# Control.net
KiCad netlist of a schematic drawn in EAGLE
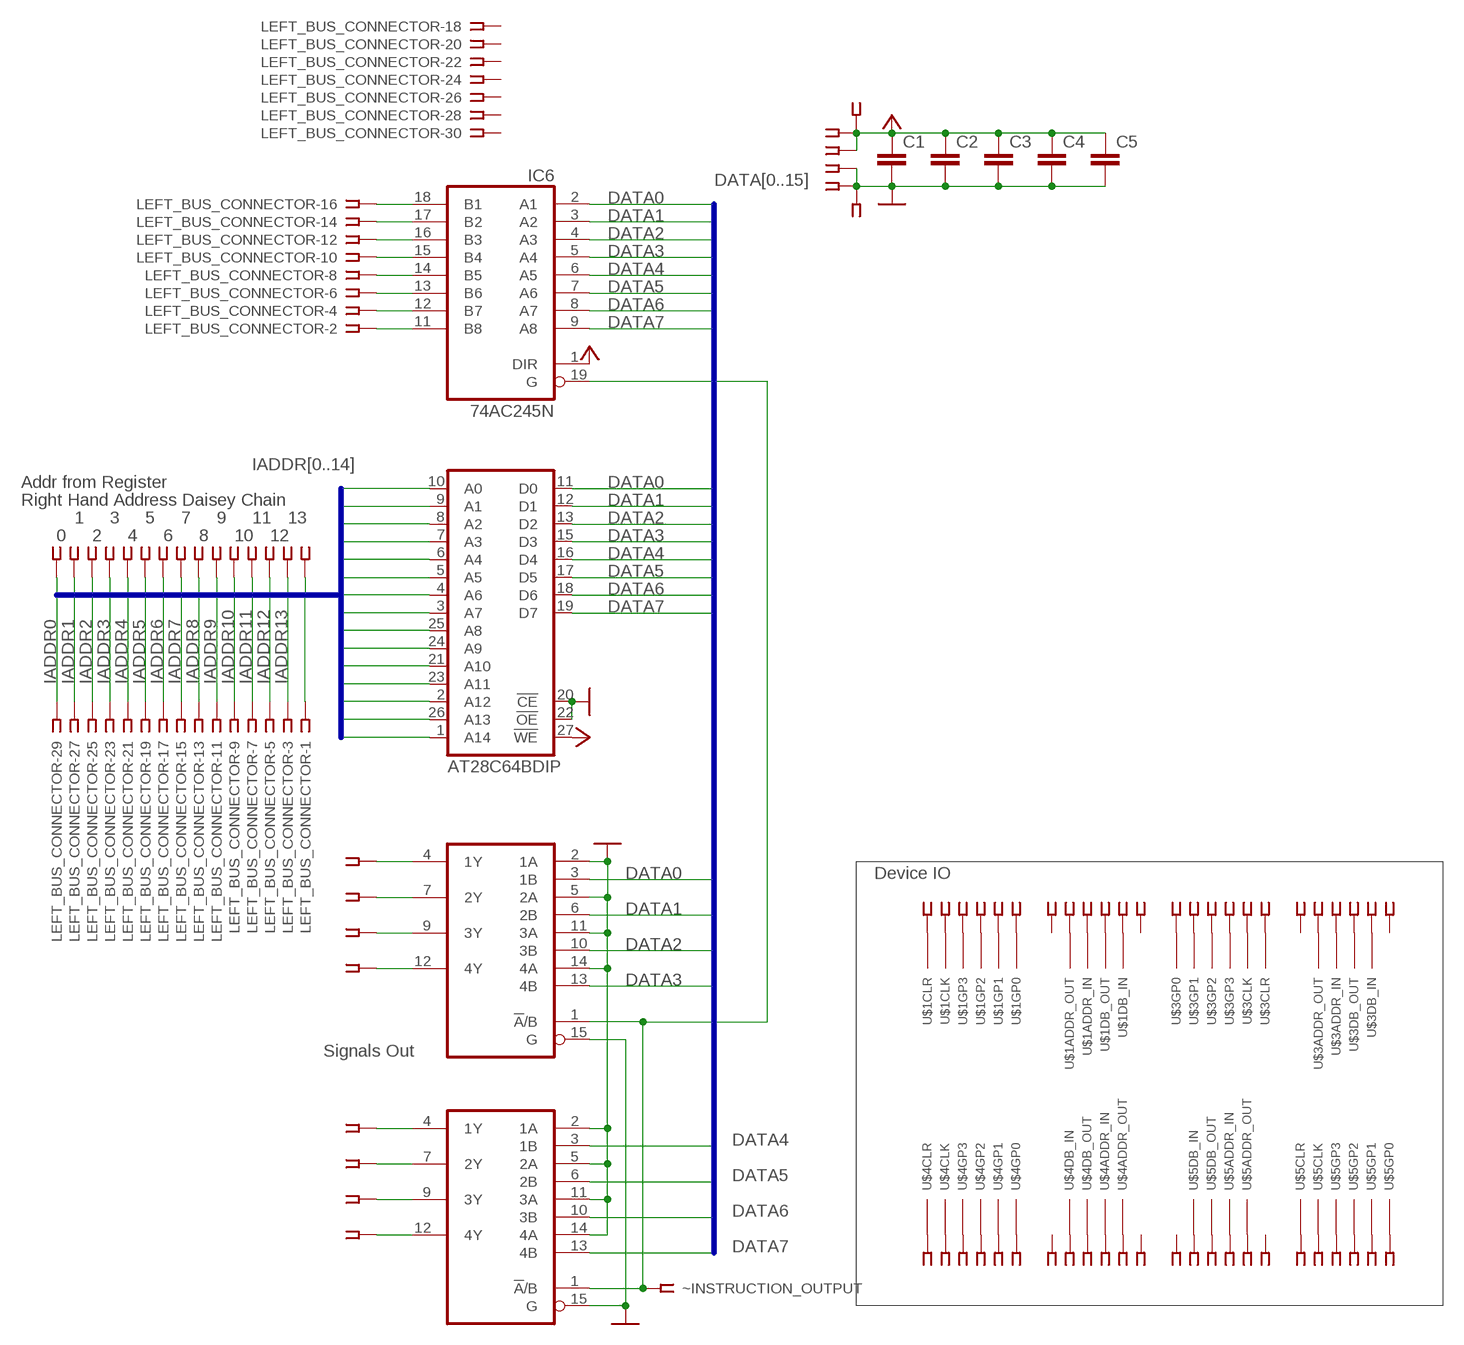
[diagram p0: schematic, sheet 1]

(export (version "E")
  (design (tool "Eeschema 10.0.6"))
  (components
    (comp (ref "C1")
      (value "C2.5/2")
      (footprint "eagle-import:C2.5-2")
      (libsource (lib "eagle-import") (part "C2.5/2"))
    )
    (comp (ref "C2")
      (value "C2.5/2")
      (footprint "eagle-import:C2.5-2")
      (libsource (lib "eagle-import") (part "C2.5/2"))
    )
    (comp (ref "C3")
      (value "C2.5/2")
      (footprint "eagle-import:C2.5-2")
      (libsource (lib "eagle-import") (part "C2.5/2"))
    )
    (comp (ref "C4")
      (value "C2.5/2")
      (footprint "eagle-import:C2.5-2")
      (libsource (lib "eagle-import") (part "C2.5/2"))
    )
    (comp (ref "C5")
      (value "C2.5/2")
      (footprint "eagle-import:C2.5-2")
      (libsource (lib "eagle-import") (part "C2.5/2"))
    )
    (comp (ref "IC4")
      (value "74AC157N")
      (footprint "eagle-import:DIL16")
      (libsource (lib "eagle-import") (part "74157NAC"))
    )
    (comp (ref "IC5")
      (value "74AC157N")
      (footprint "eagle-import:DIL16")
      (libsource (lib "eagle-import") (part "74157NAC"))
    )
    (comp (ref "IC6")
      (value "74AC245N")
      (footprint "eagle-import:DIL20")
      (libsource (lib "eagle-import") (part "74245NAC"))
    )
    (comp (ref "LEFT_BUS_CONNECTOR")
      (value "SSW-115-02-G-D")
      (footprint "eagle-import:SSW-115-02-G-D")
      (fields (field (name "MF") "Samtec Inc."))
      (libsource (lib "eagle-import") (part "SSW-115-02-G-D"))
    )
    (comp (ref "MEZZANINE")
      (value "SSW-104-02-G-S")
      (footprint "eagle-import:SSW-104-02-G-S")
      (fields (field (name "MF") "Samtec Inc."))
      (libsource (lib "eagle-import") (part "SSW-104-02-G-S"))
    )
    (comp (ref "U$1")
      (value "CONTROL_SIG-INT")
      (footprint "eagle-import:CONTROL_SIG-INT-FOOT")
      (libsource (lib "eagle-import") (part "CONTROL_SIG-INT"))
    )
    (comp (ref "U$2")
      (value "AT28C64BDIP")
      (footprint "eagle-import:DIP28-WIDE")
      (libsource (lib "eagle-import") (part "AT28C64BDIP"))
    )
    (comp (ref "U$3")
      (value "CONTROL_SIG-INT")
      (footprint "eagle-import:CONTROL_SIG-INT-FOOT")
      (libsource (lib "eagle-import") (part "CONTROL_SIG-INT"))
    )
    (comp (ref "U$4")
      (value "CONTROL_SIG-INT")
      (footprint "eagle-import:CONTROL_SIG-INT-FOOT")
      (libsource (lib "eagle-import") (part "CONTROL_SIG-INT"))
    )
    (comp (ref "U$5")
      (value "CONTROL_SIG-INT")
      (footprint "eagle-import:CONTROL_SIG-INT-FOOT")
      (libsource (lib "eagle-import") (part "CONTROL_SIG-INT"))
    )
    (comp (ref "X1")
      (value "SSW-106-02-G-S")
      (footprint "eagle-import:SSW-106-02-G-S")
      (fields (field (name "MF") "Samtec Inc."))
      (libsource (lib "eagle-import") (part "SSW-106-02-G-S"))
    )
    (comp (ref "X2")
      (value "SSW-106-02-G-S")
      (footprint "eagle-import:SSW-106-02-G-S")
      (fields (field (name "MF") "Samtec Inc."))
      (libsource (lib "eagle-import") (part "SSW-106-02-G-S"))
    )
    (comp (ref "X3")
      (value "SSW-106-02-G-S")
      (footprint "eagle-import:SSW-106-02-G-S")
      (fields (field (name "MF") "Samtec Inc."))
      (libsource (lib "eagle-import") (part "SSW-106-02-G-S"))
    )
    (comp (ref "X4")
      (value "SSW-106-02-G-S")
      (footprint "eagle-import:SSW-106-02-G-S")
      (fields (field (name "MF") "Samtec Inc."))
      (libsource (lib "eagle-import") (part "SSW-106-02-G-S"))
    )
    (comp (ref "X5")
      (value "SSW-108-02-G-S")
      (footprint "eagle-import:SSW-108-02-G-S")
      (fields (field (name "MF") "Samtec Inc."))
      (libsource (lib "eagle-import") (part "SSW-108-02-G-S"))
    )
    (comp (ref "X6")
      (value "SSW-106-02-G-S")
      (footprint "eagle-import:SSW-106-02-G-S")
      (fields (field (name "MF") "Samtec Inc."))
      (libsource (lib "eagle-import") (part "SSW-106-02-G-S"))
    )
    (comp (ref "X7")
      (value "SSW-106-02-G-S")
      (footprint "eagle-import:SSW-106-02-G-S")
      (fields (field (name "MF") "Samtec Inc."))
      (libsource (lib "eagle-import") (part "SSW-106-02-G-S"))
    )
    (comp (ref "X8")
      (value "SSW-106-02-G-S")
      (footprint "eagle-import:SSW-106-02-G-S")
      (fields (field (name "MF") "Samtec Inc."))
      (libsource (lib "eagle-import") (part "SSW-106-02-G-S"))
    )
    (comp (ref "X9")
      (value "SSW-106-02-G-S")
      (footprint "eagle-import:SSW-106-02-G-S")
      (fields (field (name "MF") "Samtec Inc."))
      (libsource (lib "eagle-import") (part "SSW-106-02-G-S"))
    )
    (comp (ref "X11")
      (value "SSW-102-02-G-S")
      (footprint "eagle-import:SSW-102-02-G-S")
      (fields (field (name "MF") "Samtec Inc."))
      (libsource (lib "eagle-import") (part "SSW-102-02-G-S"))
    )
    (comp (ref "X12")
      (value "SSW-115-02-G-S")
      (footprint "eagle-import:SSW-115-02-G-S")
      (fields (field (name "MF") "Samtec Inc."))
      (libsource (lib "eagle-import") (part "SSW-115-02-G-S"))
    )
    (comp (ref "~INSTRUCTION_OUTPUT")
      (value "SSW-101-02-G-S")
      (footprint "eagle-import:SSW-101-02-G-S")
      (fields (field (name "MF") "Samtec Inc."))
      (libsource (lib "eagle-import") (part "SSW-101-02-G-S"))
    )
  )
  (nets
    (net (code "1") (name "/DATA0") (class "Default")
      (node (ref "IC4") (pin "3") (pinfunction "1B_3") (pintype "input"))
      (node (ref "IC6") (pin "2") (pinfunction "A1_2") (pintype "bidirectional"))
      (node (ref "U$2") (pin "11") (pinfunction "D0_11") (pintype "bidirectional"))
    )
    (net (code "2") (name "/DATA1") (class "Default")
      (node (ref "IC4") (pin "6") (pinfunction "2B_6") (pintype "input"))
      (node (ref "IC6") (pin "3") (pinfunction "A2_3") (pintype "bidirectional"))
      (node (ref "U$2") (pin "12") (pinfunction "D1_12") (pintype "bidirectional"))
    )
    (net (code "3") (name "/DATA2") (class "Default")
      (node (ref "IC4") (pin "10") (pinfunction "3B_10") (pintype "input"))
      (node (ref "IC6") (pin "4") (pinfunction "A3_4") (pintype "bidirectional"))
      (node (ref "U$2") (pin "13") (pinfunction "D2_13") (pintype "bidirectional"))
    )
    (net (code "4") (name "/DATA3") (class "Default")
      (node (ref "IC4") (pin "13") (pinfunction "4B_13") (pintype "input"))
      (node (ref "IC6") (pin "5") (pinfunction "A4_5") (pintype "bidirectional"))
      (node (ref "U$2") (pin "15") (pinfunction "D3_15") (pintype "bidirectional"))
    )
    (net (code "5") (name "/DATA4") (class "Default")
      (node (ref "IC5") (pin "3") (pinfunction "1B_3") (pintype "input"))
      (node (ref "IC6") (pin "6") (pinfunction "A5_6") (pintype "bidirectional"))
      (node (ref "U$2") (pin "16") (pinfunction "D4_16") (pintype "bidirectional"))
    )
    (net (code "6") (name "/DATA5") (class "Default")
      (node (ref "IC5") (pin "6") (pinfunction "2B_6") (pintype "input"))
      (node (ref "IC6") (pin "7") (pinfunction "A6_7") (pintype "bidirectional"))
      (node (ref "U$2") (pin "17") (pinfunction "D5_17") (pintype "bidirectional"))
    )
    (net (code "7") (name "/DATA6") (class "Default")
      (node (ref "IC5") (pin "10") (pinfunction "3B_10") (pintype "input"))
      (node (ref "IC6") (pin "8") (pinfunction "A7_8") (pintype "bidirectional"))
      (node (ref "U$2") (pin "18") (pinfunction "D6_18") (pintype "bidirectional"))
    )
    (net (code "8") (name "/DATA7") (class "Default")
      (node (ref "IC5") (pin "13") (pinfunction "4B_13") (pintype "input"))
      (node (ref "IC6") (pin "9") (pinfunction "A8_9") (pintype "bidirectional"))
      (node (ref "U$2") (pin "19") (pinfunction "D7_19") (pintype "bidirectional"))
    )
    (net (code "9") (name "/IADDR0") (class "Default")
      (node (ref "LEFT_BUS_CONNECTOR") (pin "29") (pinfunction "1_29") (pintype "passive"))
      (node (ref "U$2") (pin "10") (pinfunction "A0_10") (pintype "input"))
      (node (ref "X12") (pin "1") (pinfunction "1_1") (pintype "passive"))
    )
    (net (code "10") (name "/IADDR1") (class "Default")
      (node (ref "LEFT_BUS_CONNECTOR") (pin "27") (pinfunction "1_27") (pintype "passive"))
      (node (ref "U$2") (pin "9") (pinfunction "A1_9") (pintype "input"))
      (node (ref "X12") (pin "2") (pinfunction "1_2") (pintype "passive"))
    )
    (net (code "11") (name "/IADDR2") (class "Default")
      (node (ref "LEFT_BUS_CONNECTOR") (pin "25") (pinfunction "1_25") (pintype "passive"))
      (node (ref "U$2") (pin "8") (pinfunction "A2_8") (pintype "input"))
      (node (ref "X12") (pin "3") (pinfunction "1_3") (pintype "passive"))
    )
    (net (code "12") (name "/IADDR3") (class "Default")
      (node (ref "LEFT_BUS_CONNECTOR") (pin "23") (pinfunction "1_23") (pintype "passive"))
      (node (ref "U$2") (pin "7") (pinfunction "A3_7") (pintype "input"))
      (node (ref "X12") (pin "4") (pinfunction "1_4") (pintype "passive"))
    )
    (net (code "13") (name "/IADDR4") (class "Default")
      (node (ref "LEFT_BUS_CONNECTOR") (pin "21") (pinfunction "1_21") (pintype "passive"))
      (node (ref "U$2") (pin "6") (pinfunction "A4_6") (pintype "input"))
      (node (ref "X12") (pin "5") (pinfunction "1_5") (pintype "passive"))
    )
    (net (code "14") (name "/IADDR5") (class "Default")
      (node (ref "LEFT_BUS_CONNECTOR") (pin "19") (pinfunction "1_19") (pintype "passive"))
      (node (ref "U$2") (pin "5") (pinfunction "A5_5") (pintype "input"))
      (node (ref "X12") (pin "6") (pinfunction "1_6") (pintype "passive"))
    )
    (net (code "15") (name "/IADDR6") (class "Default")
      (node (ref "LEFT_BUS_CONNECTOR") (pin "17") (pinfunction "1_17") (pintype "passive"))
      (node (ref "U$2") (pin "4") (pinfunction "A6_4") (pintype "input"))
      (node (ref "X12") (pin "7") (pinfunction "1_7") (pintype "passive"))
    )
    (net (code "16") (name "/IADDR7") (class "Default")
      (node (ref "LEFT_BUS_CONNECTOR") (pin "15") (pinfunction "1_15") (pintype "passive"))
      (node (ref "U$2") (pin "3") (pinfunction "A7_3") (pintype "input"))
      (node (ref "X12") (pin "8") (pinfunction "1_8") (pintype "passive"))
    )
    (net (code "17") (name "/IADDR8") (class "Default")
      (node (ref "LEFT_BUS_CONNECTOR") (pin "13") (pinfunction "1_13") (pintype "passive"))
      (node (ref "U$2") (pin "25") (pinfunction "A8_25") (pintype "input"))
      (node (ref "X12") (pin "9") (pinfunction "1_9") (pintype "passive"))
    )
    (net (code "18") (name "/IADDR9") (class "Default")
      (node (ref "LEFT_BUS_CONNECTOR") (pin "11") (pinfunction "1_11") (pintype "passive"))
      (node (ref "U$2") (pin "24") (pinfunction "A9_24") (pintype "input"))
      (node (ref "X12") (pin "10") (pinfunction "1_10") (pintype "passive"))
    )
    (net (code "19") (name "/IADDR10") (class "Default")
      (node (ref "LEFT_BUS_CONNECTOR") (pin "9") (pinfunction "1_9") (pintype "passive"))
      (node (ref "U$2") (pin "21") (pinfunction "A10_21") (pintype "input"))
      (node (ref "X12") (pin "11") (pinfunction "1_11") (pintype "passive"))
    )
    (net (code "20") (name "/IADDR11") (class "Default")
      (node (ref "LEFT_BUS_CONNECTOR") (pin "7") (pinfunction "1_7") (pintype "passive"))
      (node (ref "U$2") (pin "23") (pinfunction "A11_23") (pintype "input"))
      (node (ref "X12") (pin "12") (pinfunction "1_12") (pintype "passive"))
    )
    (net (code "21") (name "/IADDR12") (class "Default")
      (node (ref "LEFT_BUS_CONNECTOR") (pin "5") (pinfunction "1_5") (pintype "passive"))
      (node (ref "U$2") (pin "2") (pinfunction "A12_2") (pintype "input"))
      (node (ref "X12") (pin "13") (pinfunction "1_13") (pintype "passive"))
    )
    (net (code "22") (name "/IADDR13") (class "Default")
      (node (ref "LEFT_BUS_CONNECTOR") (pin "3") (pinfunction "1_3") (pintype "passive"))
      (node (ref "U$2") (pin "26") (pinfunction "A13_26") (pintype "input"))
      (node (ref "X12") (pin "14") (pinfunction "1_14") (pintype "passive"))
    )
    (net (code "23") (name "/IADDR14") (class "Default")
      (node (ref "LEFT_BUS_CONNECTOR") (pin "1") (pinfunction "1_1") (pintype "passive"))
      (node (ref "U$2") (pin "1") (pinfunction "A14_1") (pintype "input"))
      (node (ref "X12") (pin "15") (pinfunction "1_15") (pintype "passive"))
    )
    (net (code "25") (name "GND") (class "Default")
      (node (ref "C1") (pin "2") (pinfunction "2_2") (pintype "passive"))
      (node (ref "C2") (pin "2") (pinfunction "2_2") (pintype "passive"))
      (node (ref "C3") (pin "2") (pinfunction "2_2") (pintype "passive"))
      (node (ref "C4") (pin "2") (pinfunction "2_2") (pintype "passive"))
      (node (ref "C5") (pin "2") (pinfunction "2_2") (pintype "passive"))
      (node (ref "IC4") (pin "11") (pinfunction "3A_11") (pintype "input"))
      (node (ref "IC4") (pin "14") (pinfunction "4A_14") (pintype "input"))
      (node (ref "IC4") (pin "15") (pinfunction "G_15") (pintype "input"))
      (node (ref "IC4") (pin "2") (pinfunction "1A_2") (pintype "input"))
      (node (ref "IC4") (pin "5") (pinfunction "2A_5") (pintype "input"))
      (node (ref "IC5") (pin "11") (pinfunction "3A_11") (pintype "input"))
      (node (ref "IC5") (pin "14") (pinfunction "4A_14") (pintype "input"))
      (node (ref "IC5") (pin "15") (pinfunction "G_15") (pintype "input"))
      (node (ref "IC5") (pin "2") (pinfunction "1A_2") (pintype "input"))
      (node (ref "IC5") (pin "5") (pinfunction "2A_5") (pintype "input"))
      (node (ref "MEZZANINE") (pin "3") (pinfunction "1_3") (pintype "passive"))
      (node (ref "MEZZANINE") (pin "4") (pinfunction "1_4") (pintype "passive"))
      (node (ref "U$2") (pin "20") (pinfunction "~{CE}_20") (pintype "input"))
      (node (ref "U$2") (pin "22") (pinfunction "~{OE}_22") (pintype "input"))
      (node (ref "X11") (pin "2") (pinfunction "1_2") (pintype "passive"))
    )
    (net (code "26") (name "Net-(IC4A-1Y)") (class "Default")
      (node (ref "IC4") (pin "4") (pinfunction "1Y_4") (pintype "output"))
      (node (ref "X5") (pin "1") (pinfunction "1_1") (pintype "passive"))
    )
    (net (code "27") (name "Net-(IC4A-2Y)") (class "Default")
      (node (ref "IC4") (pin "7") (pinfunction "2Y_7") (pintype "output"))
      (node (ref "X5") (pin "2") (pinfunction "1_2") (pintype "passive"))
    )
    (net (code "28") (name "Net-(IC4A-3Y)") (class "Default")
      (node (ref "IC4") (pin "9") (pinfunction "3Y_9") (pintype "output"))
      (node (ref "X5") (pin "3") (pinfunction "1_3") (pintype "passive"))
    )
    (net (code "29") (name "Net-(IC4A-4Y)") (class "Default")
      (node (ref "IC4") (pin "12") (pinfunction "4Y_12") (pintype "output"))
      (node (ref "X5") (pin "4") (pinfunction "1_4") (pintype "passive"))
    )
    (net (code "30") (name "Net-(IC4A-~{A}{slash}B)") (class "Default")
      (node (ref "IC4") (pin "1") (pinfunction "~{A}/B_1") (pintype "input"))
      (node (ref "IC5") (pin "1") (pinfunction "~{A}/B_1") (pintype "input"))
      (node (ref "IC6") (pin "19") (pinfunction "G_19") (pintype "input"))
      (node (ref "~INSTRUCTION_OUTPUT") (pin "1") (pinfunction "1_1") (pintype "passive"))
    )
    (net (code "31") (name "Net-(IC5A-1Y)") (class "Default")
      (node (ref "IC5") (pin "4") (pinfunction "1Y_4") (pintype "output"))
      (node (ref "X5") (pin "5") (pinfunction "1_5") (pintype "passive"))
    )
    (net (code "32") (name "Net-(IC5A-2Y)") (class "Default")
      (node (ref "IC5") (pin "7") (pinfunction "2Y_7") (pintype "output"))
      (node (ref "X5") (pin "6") (pinfunction "1_6") (pintype "passive"))
    )
    (net (code "33") (name "Net-(IC5A-3Y)") (class "Default")
      (node (ref "IC5") (pin "9") (pinfunction "3Y_9") (pintype "output"))
      (node (ref "X5") (pin "7") (pinfunction "1_7") (pintype "passive"))
    )
    (net (code "34") (name "Net-(IC5A-4Y)") (class "Default")
      (node (ref "IC5") (pin "12") (pinfunction "4Y_12") (pintype "output"))
      (node (ref "X5") (pin "8") (pinfunction "1_8") (pintype "passive"))
    )
    (net (code "35") (name "Net-(IC6A-B1)") (class "Default")
      (node (ref "IC6") (pin "18") (pinfunction "B1_18") (pintype "bidirectional"))
      (node (ref "LEFT_BUS_CONNECTOR") (pin "16") (pinfunction "1_16") (pintype "passive"))
    )
    (net (code "36") (name "Net-(IC6A-B2)") (class "Default")
      (node (ref "IC6") (pin "17") (pinfunction "B2_17") (pintype "bidirectional"))
      (node (ref "LEFT_BUS_CONNECTOR") (pin "14") (pinfunction "1_14") (pintype "passive"))
    )
    (net (code "37") (name "Net-(IC6A-B3)") (class "Default")
      (node (ref "IC6") (pin "16") (pinfunction "B3_16") (pintype "bidirectional"))
      (node (ref "LEFT_BUS_CONNECTOR") (pin "12") (pinfunction "1_12") (pintype "passive"))
    )
    (net (code "38") (name "Net-(IC6A-B4)") (class "Default")
      (node (ref "IC6") (pin "15") (pinfunction "B4_15") (pintype "bidirectional"))
      (node (ref "LEFT_BUS_CONNECTOR") (pin "10") (pinfunction "1_10") (pintype "passive"))
    )
    (net (code "39") (name "Net-(IC6A-B5)") (class "Default")
      (node (ref "IC6") (pin "14") (pinfunction "B5_14") (pintype "bidirectional"))
      (node (ref "LEFT_BUS_CONNECTOR") (pin "8") (pinfunction "1_8") (pintype "passive"))
    )
    (net (code "40") (name "Net-(IC6A-B6)") (class "Default")
      (node (ref "IC6") (pin "13") (pinfunction "B6_13") (pintype "bidirectional"))
      (node (ref "LEFT_BUS_CONNECTOR") (pin "6") (pinfunction "1_6") (pintype "passive"))
    )
    (net (code "41") (name "Net-(IC6A-B7)") (class "Default")
      (node (ref "IC6") (pin "12") (pinfunction "B7_12") (pintype "bidirectional"))
      (node (ref "LEFT_BUS_CONNECTOR") (pin "4") (pinfunction "1_4") (pintype "passive"))
    )
    (net (code "42") (name "Net-(IC6A-B8)") (class "Default")
      (node (ref "IC6") (pin "11") (pinfunction "B8_11") (pintype "bidirectional"))
      (node (ref "LEFT_BUS_CONNECTOR") (pin "2") (pinfunction "1_2") (pintype "passive"))
    )
    (net (code "43") (name "Net-(U$1A-0)") (class "Default")
      (node (ref "U$1") (pin "ADDR_IN") (pinfunction "0_ADDR_IN") (pintype "bidirectional"))
      (node (ref "X2") (pin "4") (pinfunction "1_4") (pintype "passive"))
    )
    (net (code "44") (name "Net-(U$1B-0)") (class "Default")
      (node (ref "U$1") (pin "ADDR_OT") (pinfunction "0_ADDR_OT") (pintype "bidirectional"))
      (node (ref "X2") (pin "5") (pinfunction "1_5") (pintype "passive"))
    )
    (net (code "45") (name "Net-(U$1C-0)") (class "Default")
      (node (ref "U$1") (pin "CLK") (pinfunction "0_CLK") (pintype "bidirectional"))
      (node (ref "X1") (pin "2") (pinfunction "1_2") (pintype "passive"))
    )
    (net (code "46") (name "Net-(U$1D-0)") (class "Default")
      (node (ref "U$1") (pin "CLR") (pinfunction "0_CLR") (pintype "bidirectional"))
      (node (ref "X1") (pin "1") (pinfunction "1_1") (pintype "passive"))
    )
    (net (code "47") (name "Net-(U$1E-0)") (class "Default")
      (node (ref "U$1") (pin "DB_IN") (pinfunction "0_DB_IN") (pintype "bidirectional"))
      (node (ref "X2") (pin "2") (pinfunction "1_2") (pintype "passive"))
    )
    (net (code "48") (name "Net-(U$1F-0)") (class "Default")
      (node (ref "U$1") (pin "DB_OUT") (pinfunction "0_DB_OUT") (pintype "bidirectional"))
      (node (ref "X2") (pin "3") (pinfunction "1_3") (pintype "passive"))
    )
    (net (code "49") (name "Net-(U$1H-0)") (class "Default")
      (node (ref "U$1") (pin "GP0") (pinfunction "0_GP0") (pintype "bidirectional"))
      (node (ref "X1") (pin "6") (pinfunction "1_6") (pintype "passive"))
    )
    (net (code "50") (name "Net-(U$1I-0)") (class "Default")
      (node (ref "U$1") (pin "GP1") (pinfunction "0_GP1") (pintype "bidirectional"))
      (node (ref "X1") (pin "5") (pinfunction "1_5") (pintype "passive"))
    )
    (net (code "51") (name "Net-(U$1J-0)") (class "Default")
      (node (ref "U$1") (pin "GP2") (pinfunction "0_GP2") (pintype "bidirectional"))
      (node (ref "X1") (pin "4") (pinfunction "1_4") (pintype "passive"))
    )
    (net (code "52") (name "Net-(U$1K-0)") (class "Default")
      (node (ref "U$1") (pin "GP3") (pinfunction "0_GP3") (pintype "bidirectional"))
      (node (ref "X1") (pin "3") (pinfunction "1_3") (pintype "passive"))
    )
    (net (code "53") (name "Net-(U$3A-0)") (class "Default")
      (node (ref "U$3") (pin "ADDR_IN") (pinfunction "0_ADDR_IN") (pintype "bidirectional"))
      (node (ref "X4") (pin "4") (pinfunction "1_4") (pintype "passive"))
    )
    (net (code "54") (name "Net-(U$3B-0)") (class "Default")
      (node (ref "U$3") (pin "ADDR_OT") (pinfunction "0_ADDR_OT") (pintype "bidirectional"))
      (node (ref "X4") (pin "5") (pinfunction "1_5") (pintype "passive"))
    )
    (net (code "55") (name "Net-(U$3C-0)") (class "Default")
      (node (ref "U$3") (pin "CLK") (pinfunction "0_CLK") (pintype "bidirectional"))
      (node (ref "X3") (pin "2") (pinfunction "1_2") (pintype "passive"))
    )
    (net (code "56") (name "Net-(U$3D-0)") (class "Default")
      (node (ref "U$3") (pin "CLR") (pinfunction "0_CLR") (pintype "bidirectional"))
      (node (ref "X3") (pin "1") (pinfunction "1_1") (pintype "passive"))
    )
    (net (code "57") (name "Net-(U$3E-0)") (class "Default")
      (node (ref "U$3") (pin "DB_IN") (pinfunction "0_DB_IN") (pintype "bidirectional"))
      (node (ref "X4") (pin "2") (pinfunction "1_2") (pintype "passive"))
    )
    (net (code "58") (name "Net-(U$3F-0)") (class "Default")
      (node (ref "U$3") (pin "DB_OUT") (pinfunction "0_DB_OUT") (pintype "bidirectional"))
      (node (ref "X4") (pin "3") (pinfunction "1_3") (pintype "passive"))
    )
    (net (code "59") (name "Net-(U$3H-0)") (class "Default")
      (node (ref "U$3") (pin "GP0") (pinfunction "0_GP0") (pintype "bidirectional"))
      (node (ref "X3") (pin "6") (pinfunction "1_6") (pintype "passive"))
    )
    (net (code "60") (name "Net-(U$3I-0)") (class "Default")
      (node (ref "U$3") (pin "GP1") (pinfunction "0_GP1") (pintype "bidirectional"))
      (node (ref "X3") (pin "5") (pinfunction "1_5") (pintype "passive"))
    )
    (net (code "61") (name "Net-(U$3J-0)") (class "Default")
      (node (ref "U$3") (pin "GP2") (pinfunction "0_GP2") (pintype "bidirectional"))
      (node (ref "X3") (pin "4") (pinfunction "1_4") (pintype "passive"))
    )
    (net (code "62") (name "Net-(U$3K-0)") (class "Default")
      (node (ref "U$3") (pin "GP3") (pinfunction "0_GP3") (pintype "bidirectional"))
      (node (ref "X3") (pin "3") (pinfunction "1_3") (pintype "passive"))
    )
    (net (code "63") (name "Net-(U$4A-0)") (class "Default")
      (node (ref "U$4") (pin "ADDR_IN") (pinfunction "0_ADDR_IN") (pintype "bidirectional"))
      (node (ref "X8") (pin "4") (pinfunction "1_4") (pintype "passive"))
    )
    (net (code "64") (name "Net-(U$4B-0)") (class "Default")
      (node (ref "U$4") (pin "ADDR_OT") (pinfunction "0_ADDR_OT") (pintype "bidirectional"))
      (node (ref "X8") (pin "5") (pinfunction "1_5") (pintype "passive"))
    )
    (net (code "65") (name "Net-(U$4C-0)") (class "Default")
      (node (ref "U$4") (pin "CLK") (pinfunction "0_CLK") (pintype "bidirectional"))
      (node (ref "X9") (pin "2") (pinfunction "1_2") (pintype "passive"))
    )
    (net (code "66") (name "Net-(U$4D-0)") (class "Default")
      (node (ref "U$4") (pin "CLR") (pinfunction "0_CLR") (pintype "bidirectional"))
      (node (ref "X9") (pin "1") (pinfunction "1_1") (pintype "passive"))
    )
    (net (code "67") (name "Net-(U$4E-0)") (class "Default")
      (node (ref "U$4") (pin "DB_IN") (pinfunction "0_DB_IN") (pintype "bidirectional"))
      (node (ref "X8") (pin "2") (pinfunction "1_2") (pintype "passive"))
    )
    (net (code "68") (name "Net-(U$4F-0)") (class "Default")
      (node (ref "U$4") (pin "DB_OUT") (pinfunction "0_DB_OUT") (pintype "bidirectional"))
      (node (ref "X8") (pin "3") (pinfunction "1_3") (pintype "passive"))
    )
    (net (code "69") (name "Net-(U$4H-0)") (class "Default")
      (node (ref "U$4") (pin "GP0") (pinfunction "0_GP0") (pintype "bidirectional"))
      (node (ref "X9") (pin "6") (pinfunction "1_6") (pintype "passive"))
    )
    (net (code "70") (name "Net-(U$4I-0)") (class "Default")
      (node (ref "U$4") (pin "GP1") (pinfunction "0_GP1") (pintype "bidirectional"))
      (node (ref "X9") (pin "5") (pinfunction "1_5") (pintype "passive"))
    )
    (net (code "71") (name "Net-(U$4J-0)") (class "Default")
      (node (ref "U$4") (pin "GP2") (pinfunction "0_GP2") (pintype "bidirectional"))
      (node (ref "X9") (pin "4") (pinfunction "1_4") (pintype "passive"))
    )
    (net (code "72") (name "Net-(U$4K-0)") (class "Default")
      (node (ref "U$4") (pin "GP3") (pinfunction "0_GP3") (pintype "bidirectional"))
      (node (ref "X9") (pin "3") (pinfunction "1_3") (pintype "passive"))
    )
    (net (code "73") (name "Net-(U$5A-0)") (class "Default")
      (node (ref "U$5") (pin "ADDR_IN") (pinfunction "0_ADDR_IN") (pintype "bidirectional"))
      (node (ref "X7") (pin "4") (pinfunction "1_4") (pintype "passive"))
    )
    (net (code "74") (name "Net-(U$5B-0)") (class "Default")
      (node (ref "U$5") (pin "ADDR_OT") (pinfunction "0_ADDR_OT") (pintype "bidirectional"))
      (node (ref "X7") (pin "5") (pinfunction "1_5") (pintype "passive"))
    )
    (net (code "75") (name "Net-(U$5C-0)") (class "Default")
      (node (ref "U$5") (pin "CLK") (pinfunction "0_CLK") (pintype "bidirectional"))
      (node (ref "X6") (pin "2") (pinfunction "1_2") (pintype "passive"))
    )
    (net (code "76") (name "Net-(U$5D-0)") (class "Default")
      (node (ref "U$5") (pin "CLR") (pinfunction "0_CLR") (pintype "bidirectional"))
      (node (ref "X6") (pin "1") (pinfunction "1_1") (pintype "passive"))
    )
    (net (code "77") (name "Net-(U$5E-0)") (class "Default")
      (node (ref "U$5") (pin "DB_IN") (pinfunction "0_DB_IN") (pintype "bidirectional"))
      (node (ref "X7") (pin "2") (pinfunction "1_2") (pintype "passive"))
    )
    (net (code "78") (name "Net-(U$5F-0)") (class "Default")
      (node (ref "U$5") (pin "DB_OUT") (pinfunction "0_DB_OUT") (pintype "bidirectional"))
      (node (ref "X7") (pin "3") (pinfunction "1_3") (pintype "passive"))
    )
    (net (code "79") (name "Net-(U$5H-0)") (class "Default")
      (node (ref "U$5") (pin "GP0") (pinfunction "0_GP0") (pintype "bidirectional"))
      (node (ref "X6") (pin "6") (pinfunction "1_6") (pintype "passive"))
    )
    (net (code "80") (name "Net-(U$5I-0)") (class "Default")
      (node (ref "U$5") (pin "GP1") (pinfunction "0_GP1") (pintype "bidirectional"))
      (node (ref "X6") (pin "5") (pinfunction "1_5") (pintype "passive"))
    )
    (net (code "81") (name "Net-(U$5J-0)") (class "Default")
      (node (ref "U$5") (pin "GP2") (pinfunction "0_GP2") (pintype "bidirectional"))
      (node (ref "X6") (pin "4") (pinfunction "1_4") (pintype "passive"))
    )
    (net (code "82") (name "Net-(U$5K-0)") (class "Default")
      (node (ref "U$5") (pin "GP3") (pinfunction "0_GP3") (pintype "bidirectional"))
      (node (ref "X6") (pin "3") (pinfunction "1_3") (pintype "passive"))
    )
    (net (code "83") (name "VCC") (class "Default")
      (node (ref "C1") (pin "1") (pinfunction "1_1") (pintype "passive"))
      (node (ref "C2") (pin "1") (pinfunction "1_1") (pintype "passive"))
      (node (ref "C3") (pin "1") (pinfunction "1_1") (pintype "passive"))
      (node (ref "C4") (pin "1") (pinfunction "1_1") (pintype "passive"))
      (node (ref "C5") (pin "1") (pinfunction "1_1") (pintype "passive"))
      (node (ref "IC6") (pin "1") (pinfunction "DIR_1") (pintype "input"))
      (node (ref "MEZZANINE") (pin "1") (pinfunction "1_1") (pintype "passive"))
      (node (ref "MEZZANINE") (pin "2") (pinfunction "1_2") (pintype "passive"))
      (node (ref "U$2") (pin "27") (pinfunction "~{WE}_27") (pintype "input"))
      (node (ref "X11") (pin "1") (pinfunction "1_1") (pintype "passive"))
    )
    (net (code "84") (name "unconnected-(LEFT_BUS_CONNECTORJ-1-Pad18)") (class "Default")
      (node (ref "LEFT_BUS_CONNECTOR") (pin "18") (pinfunction "1_18") (pintype "passive"))
    )
    (net (code "85") (name "unconnected-(LEFT_BUS_CONNECTORM-1-Pad20)") (class "Default")
      (node (ref "LEFT_BUS_CONNECTOR") (pin "20") (pinfunction "1_20") (pintype "passive"))
    )
    (net (code "86") (name "unconnected-(LEFT_BUS_CONNECTORO-1-Pad22)") (class "Default")
      (node (ref "LEFT_BUS_CONNECTOR") (pin "22") (pinfunction "1_22") (pintype "passive"))
    )
    (net (code "87") (name "unconnected-(LEFT_BUS_CONNECTORQ-1-Pad24)") (class "Default")
      (node (ref "LEFT_BUS_CONNECTOR") (pin "24") (pinfunction "1_24") (pintype "passive"))
    )
    (net (code "88") (name "unconnected-(LEFT_BUS_CONNECTORS-1-Pad26)") (class "Default")
      (node (ref "LEFT_BUS_CONNECTOR") (pin "26") (pinfunction "1_26") (pintype "passive"))
    )
    (net (code "89") (name "unconnected-(LEFT_BUS_CONNECTORU-1-Pad28)") (class "Default")
      (node (ref "LEFT_BUS_CONNECTOR") (pin "28") (pinfunction "1_28") (pintype "passive"))
    )
    (net (code "90") (name "unconnected-(LEFT_BUS_CONNECTORX-1-Pad30)") (class "Default")
      (node (ref "LEFT_BUS_CONNECTOR") (pin "30") (pinfunction "1_30") (pintype "passive"))
    )
    (net (code "91") (name "unconnected-(X2-Pad1)") (class "Default")
      (node (ref "X2") (pin "1") (pinfunction "1_1") (pintype "passive"))
    )
    (net (code "92") (name "unconnected-(X2F-1-Pad6)") (class "Default")
      (node (ref "X2") (pin "6") (pinfunction "1_6") (pintype "passive"))
    )
    (net (code "93") (name "unconnected-(X4-Pad1)") (class "Default")
      (node (ref "X4") (pin "1") (pinfunction "1_1") (pintype "passive"))
    )
    (net (code "94") (name "unconnected-(X4F-1-Pad6)") (class "Default")
      (node (ref "X4") (pin "6") (pinfunction "1_6") (pintype "passive"))
    )
    (net (code "95") (name "unconnected-(X7-Pad1)") (class "Default")
      (node (ref "X7") (pin "1") (pinfunction "1_1") (pintype "passive"))
    )
    (net (code "96") (name "unconnected-(X7F-1-Pad6)") (class "Default")
      (node (ref "X7") (pin "6") (pinfunction "1_6") (pintype "passive"))
    )
    (net (code "97") (name "unconnected-(X8-Pad1)") (class "Default")
      (node (ref "X8") (pin "1") (pinfunction "1_1") (pintype "passive"))
    )
    (net (code "98") (name "unconnected-(X8F-1-Pad6)") (class "Default")
      (node (ref "X8") (pin "6") (pinfunction "1_6") (pintype "passive"))
    )
  )
)
